# Eye-of-Ord-v1_9.net
KiCad netlist of a schematic drawn in EAGLE
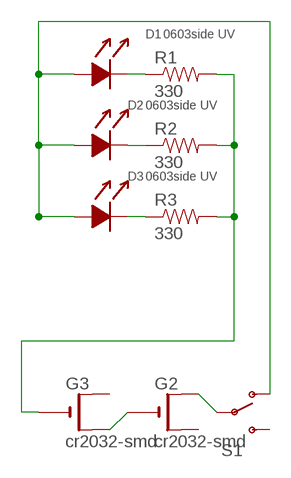
[diagram p0: schematic, sheet 1]

(export (version "E")
  (design (tool "Eeschema 10.0.6"))
  (components
    (comp (ref "D1")
      (value "0603side UV")
      (footprint "eagle-import:SMD-0603-LED-SIDE")
      (libsource (lib "eagle-import") (part "0603SIDELED"))
    )
    (comp (ref "D2")
      (value "0603side UV")
      (footprint "eagle-import:SMD-0603-LED-SIDE")
      (libsource (lib "eagle-import") (part "0603SIDELED"))
    )
    (comp (ref "D3")
      (value "0603side UV")
      (footprint "eagle-import:SMD-0603-LED-SIDE")
      (libsource (lib "eagle-import") (part "0603SIDELED"))
    )
    (comp (ref "G2")
      (value "cr2032-smd")
      (footprint "eagle-import:CR2032-SMD")
      (libsource (lib "eagle-import") (part "CR2032SMT"))
    )
    (comp (ref "G3")
      (value "cr2032-smd")
      (footprint "eagle-import:CR2032-SMD")
      (libsource (lib "eagle-import") (part "CR2032SMT"))
    )
    (comp (ref "R1")
      (value "330")
      (footprint "eagle-import:0603-RES")
      (libsource (lib "eagle-import") (part "RESISTOR0603-RES"))
    )
    (comp (ref "R2")
      (value "330")
      (footprint "eagle-import:0603-RES")
      (libsource (lib "eagle-import") (part "RESISTOR0603-RES"))
    )
    (comp (ref "R3")
      (value "330")
      (footprint "eagle-import:0603-RES")
      (libsource (lib "eagle-import") (part "RESISTOR0603-RES"))
    )
    (comp (ref "S1")
      (value "SWITCH-SPDT-SMD-A")
      (footprint "eagle-import:SWITCH-SPST-SMD-A")
      (libsource (lib "eagle-import") (part "SWITCH-SPDT-SMD-A"))
    )
  )
  (nets
    (net (code "1") (name "Net-(D1-K)") (class "Default")
      (node (ref "D1") (pin "C") (pinfunction "K_C") (pintype "bidirectional"))
      (node (ref "R1") (pin "1") (pinfunction "1_1") (pintype "passive"))
    )
    (net (code "2") (name "Net-(D2-K)") (class "Default")
      (node (ref "D2") (pin "C") (pinfunction "K_C") (pintype "bidirectional"))
      (node (ref "R2") (pin "1") (pinfunction "1_1") (pintype "passive"))
    )
    (net (code "3") (name "Net-(D3-K)") (class "Default")
      (node (ref "D3") (pin "C") (pinfunction "K_C") (pintype "bidirectional"))
      (node (ref "R3") (pin "1") (pinfunction "1_1") (pintype "passive"))
    )
    (net (code "4") (name "Net-(G2-+)") (class "Default")
      (node (ref "G2") (pin "+$1") (pinfunction "+_+$1") (pintype "passive"))
      (node (ref "S1") (pin "2") (pinfunction "P_2") (pintype "passive"))
    )
    (net (code "5") (name "Net-(G3-+1)") (class "Default")
      (node (ref "G2") (pin "-") (pinfunction "-_-") (pintype "passive"))
      (node (ref "G3") (pin "+$2") (pinfunction "+1_+$2") (pintype "passive"))
    )
    (net (code "6") (name "Net-(G3-Pad-)") (class "Default")
      (node (ref "G3") (pin "-") (pinfunction "-_-") (pintype "passive"))
      (node (ref "R1") (pin "2") (pinfunction "2_2") (pintype "passive"))
      (node (ref "R2") (pin "2") (pinfunction "2_2") (pintype "passive"))
      (node (ref "R3") (pin "2") (pinfunction "2_2") (pintype "passive"))
    )
    (net (code "7") (name "Net-(S1-O)") (class "Default")
      (node (ref "D1") (pin "A") (pinfunction "A_A") (pintype "bidirectional"))
      (node (ref "D2") (pin "A") (pinfunction "A_A") (pintype "bidirectional"))
      (node (ref "D3") (pin "A") (pinfunction "A_A") (pintype "bidirectional"))
      (node (ref "S1") (pin "1") (pinfunction "O_1") (pintype "passive"))
    )
    (net (code "8") (name "unconnected-(G2-+1-Pad+$2)") (class "Default")
      (node (ref "G2") (pin "+$2") (pinfunction "+1_+$2") (pintype "passive"))
    )
    (net (code "9") (name "unconnected-(G3-+-Pad+$1)") (class "Default")
      (node (ref "G3") (pin "+$1") (pinfunction "+_+$1") (pintype "passive"))
    )
    (net (code "10") (name "unconnected-(S1-S-Pad3)") (class "Default")
      (node (ref "S1") (pin "3") (pinfunction "S_3") (pintype "passive"))
    )
  )
)
